# BCProjectBoardV2.net
KiCad netlist of a schematic drawn in EAGLE
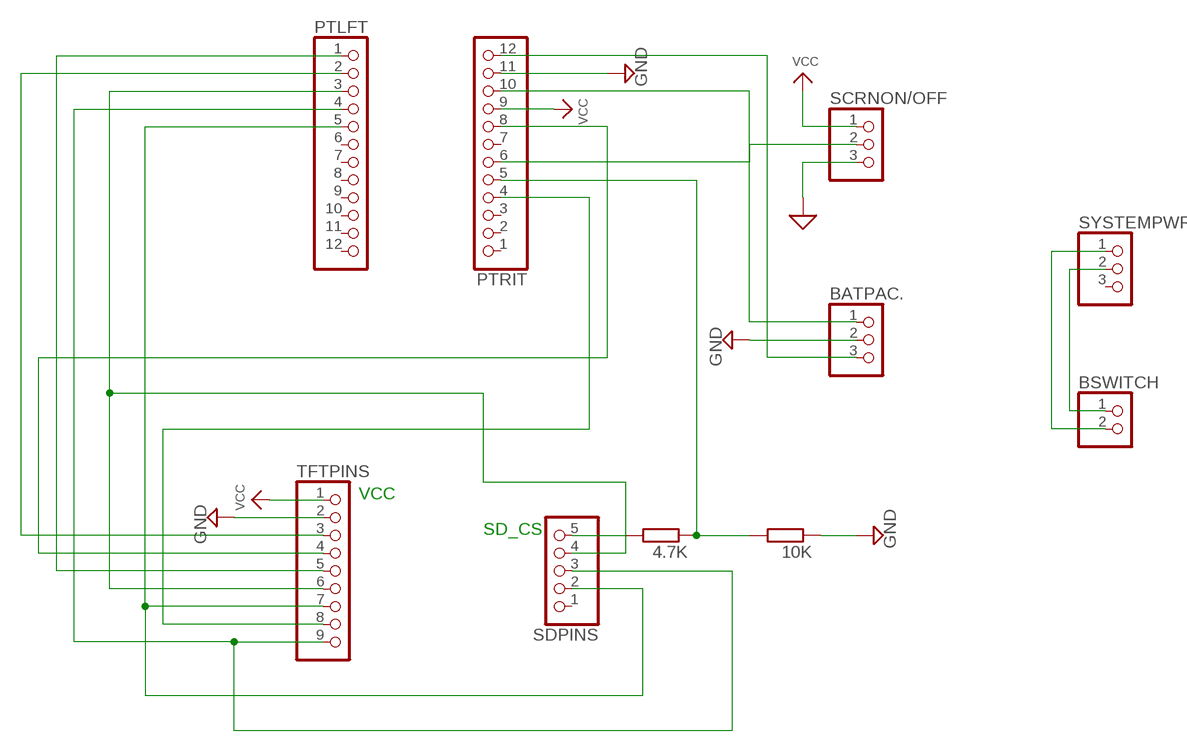
[diagram p0: schematic, sheet 1]

(export (version "E")
  (design (tool "Eeschema 10.0.6"))
  (components
    (comp (ref "4.7K")
      (value "R-EU_0204/5")
      (footprint "eagle-import:0204_5")
      (libsource (lib "eagle-import") (part "R-EU_0204/5"))
    )
    (comp (ref "10K")
      (value "R-EU_0204/5")
      (footprint "eagle-import:0204_5")
      (libsource (lib "eagle-import") (part "R-EU_0204/5"))
    )
    (comp (ref "BATPAC.")
      (value "PINHD-1X3")
      (footprint "eagle-import:1X03")
      (libsource (lib "eagle-import") (part "PINHD-1X3"))
    )
    (comp (ref "BSWITCH")
      (value "PINHD-1X2")
      (footprint "eagle-import:1X02")
      (libsource (lib "eagle-import") (part "PINHD-1X2"))
    )
    (comp (ref "PTLFT")
      (value "PINHD-1X12")
      (footprint "eagle-import:1X12")
      (libsource (lib "eagle-import") (part "PINHD-1X12"))
    )
    (comp (ref "PTRIT")
      (value "PINHD-1X12")
      (footprint "eagle-import:1X12")
      (libsource (lib "eagle-import") (part "PINHD-1X12"))
    )
    (comp (ref "SCRNON/OFF")
      (value "PINHD-1X3")
      (footprint "eagle-import:1X03")
      (libsource (lib "eagle-import") (part "PINHD-1X3"))
    )
    (comp (ref "SDPINS")
      (value "PINHD-1X5")
      (footprint "eagle-import:1X05")
      (libsource (lib "eagle-import") (part "PINHD-1X5"))
    )
    (comp (ref "SYSTEMPWR")
      (value "PINHD-1X3")
      (footprint "eagle-import:1X03")
      (libsource (lib "eagle-import") (part "PINHD-1X3"))
    )
    (comp (ref "TFTPINS")
      (value "PINHD-1X9")
      (footprint "eagle-import:1X09")
      (libsource (lib "eagle-import") (part "PINHD-1X9"))
    )
  )
  (nets
    (net (code "1") (name "GND") (class "Default")
      (node (ref "10K") (pin "1") (pinfunction "1_1") (pintype "passive"))
      (node (ref "BATPAC.") (pin "2") (pinfunction "2_2") (pintype "passive"))
      (node (ref "PTRIT") (pin "11") (pinfunction "11_11") (pintype "passive"))
      (node (ref "SCRNON/OFF") (pin "3") (pinfunction "3_3") (pintype "passive"))
      (node (ref "TFTPINS") (pin "2") (pinfunction "2_2") (pintype "passive"))
    )
    (net (code "2") (name "Net-(4.7K-Pad2)") (class "Default")
      (node (ref "4.7K") (pin "2") (pinfunction "2_2") (pintype "passive"))
      (node (ref "SDPINS") (pin "5") (pinfunction "5_5") (pintype "passive"))
    )
    (net (code "3") (name "Net-(10K-Pad2)") (class "Default")
      (node (ref "10K") (pin "2") (pinfunction "2_2") (pintype "passive"))
      (node (ref "4.7K") (pin "1") (pinfunction "1_1") (pintype "passive"))
      (node (ref "PTRIT") (pin "5") (pinfunction "5_5") (pintype "passive"))
    )
    (net (code "4") (name "Net-(BATPAC.-Pad1)") (class "Default")
      (node (ref "BATPAC.") (pin "1") (pinfunction "1_1") (pintype "passive"))
      (node (ref "PTRIT") (pin "10") (pinfunction "10_10") (pintype "passive"))
    )
    (net (code "5") (name "Net-(BATPAC.-Pad3)") (class "Default")
      (node (ref "BATPAC.") (pin "3") (pinfunction "3_3") (pintype "passive"))
      (node (ref "PTRIT") (pin "12") (pinfunction "12_12") (pintype "passive"))
    )
    (net (code "6") (name "Net-(BSWITCH-Pad1)") (class "Default")
      (node (ref "BSWITCH") (pin "1") (pinfunction "1_1") (pintype "passive"))
      (node (ref "SYSTEMPWR") (pin "2") (pinfunction "2_2") (pintype "passive"))
    )
    (net (code "7") (name "Net-(BSWITCH-Pad2)") (class "Default")
      (node (ref "BSWITCH") (pin "2") (pinfunction "2_2") (pintype "passive"))
      (node (ref "SYSTEMPWR") (pin "1") (pinfunction "1_1") (pintype "passive"))
    )
    (net (code "8") (name "Net-(PTLFT-Pad1)") (class "Default")
      (node (ref "PTLFT") (pin "1") (pinfunction "1_1") (pintype "passive"))
      (node (ref "TFTPINS") (pin "5") (pinfunction "5_5") (pintype "passive"))
    )
    (net (code "9") (name "Net-(PTLFT-Pad2)") (class "Default")
      (node (ref "PTLFT") (pin "2") (pinfunction "2_2") (pintype "passive"))
      (node (ref "TFTPINS") (pin "3") (pinfunction "3_3") (pintype "passive"))
    )
    (net (code "10") (name "Net-(PTLFT-Pad3)") (class "Default")
      (node (ref "PTLFT") (pin "3") (pinfunction "3_3") (pintype "passive"))
      (node (ref "SDPINS") (pin "4") (pinfunction "4_4") (pintype "passive"))
      (node (ref "TFTPINS") (pin "6") (pinfunction "6_6") (pintype "passive"))
    )
    (net (code "11") (name "Net-(PTLFT-Pad4)") (class "Default")
      (node (ref "PTLFT") (pin "4") (pinfunction "4_4") (pintype "passive"))
      (node (ref "SDPINS") (pin "3") (pinfunction "3_3") (pintype "passive"))
      (node (ref "TFTPINS") (pin "9") (pinfunction "9_9") (pintype "passive"))
    )
    (net (code "12") (name "Net-(PTLFT-Pad5)") (class "Default")
      (node (ref "PTLFT") (pin "5") (pinfunction "5_5") (pintype "passive"))
      (node (ref "SDPINS") (pin "2") (pinfunction "2_2") (pintype "passive"))
      (node (ref "TFTPINS") (pin "7") (pinfunction "7_7") (pintype "passive"))
    )
    (net (code "13") (name "Net-(PTRIT-Pad4)") (class "Default")
      (node (ref "PTRIT") (pin "4") (pinfunction "4_4") (pintype "passive"))
      (node (ref "TFTPINS") (pin "8") (pinfunction "8_8") (pintype "passive"))
    )
    (net (code "14") (name "Net-(PTRIT-Pad6)") (class "Default")
      (node (ref "PTRIT") (pin "6") (pinfunction "6_6") (pintype "passive"))
      (node (ref "SCRNON/OFF") (pin "2") (pinfunction "2_2") (pintype "passive"))
    )
    (net (code "15") (name "Net-(PTRIT-Pad8)") (class "Default")
      (node (ref "PTRIT") (pin "8") (pinfunction "8_8") (pintype "passive"))
      (node (ref "TFTPINS") (pin "4") (pinfunction "4_4") (pintype "passive"))
    )
    (net (code "16") (name "VCC") (class "Default")
      (node (ref "PTRIT") (pin "9") (pinfunction "9_9") (pintype "passive"))
      (node (ref "SCRNON/OFF") (pin "1") (pinfunction "1_1") (pintype "passive"))
      (node (ref "TFTPINS") (pin "1") (pinfunction "1_1") (pintype "passive"))
    )
    (net (code "17") (name "unconnected-(PTLFT-Pad6)") (class "Default")
      (node (ref "PTLFT") (pin "6") (pinfunction "6_6") (pintype "passive"))
    )
    (net (code "18") (name "unconnected-(PTLFT-Pad7)") (class "Default")
      (node (ref "PTLFT") (pin "7") (pinfunction "7_7") (pintype "passive"))
    )
    (net (code "19") (name "unconnected-(PTLFT-Pad8)") (class "Default")
      (node (ref "PTLFT") (pin "8") (pinfunction "8_8") (pintype "passive"))
    )
    (net (code "20") (name "unconnected-(PTLFT-Pad9)") (class "Default")
      (node (ref "PTLFT") (pin "9") (pinfunction "9_9") (pintype "passive"))
    )
    (net (code "21") (name "unconnected-(PTLFT-Pad10)") (class "Default")
      (node (ref "PTLFT") (pin "10") (pinfunction "10_10") (pintype "passive"))
    )
    (net (code "22") (name "unconnected-(PTLFT-Pad11)") (class "Default")
      (node (ref "PTLFT") (pin "11") (pinfunction "11_11") (pintype "passive"))
    )
    (net (code "23") (name "unconnected-(PTLFT-Pad12)") (class "Default")
      (node (ref "PTLFT") (pin "12") (pinfunction "12_12") (pintype "passive"))
    )
    (net (code "24") (name "unconnected-(PTRIT-Pad1)") (class "Default")
      (node (ref "PTRIT") (pin "1") (pinfunction "1_1") (pintype "passive"))
    )
    (net (code "25") (name "unconnected-(PTRIT-Pad2)") (class "Default")
      (node (ref "PTRIT") (pin "2") (pinfunction "2_2") (pintype "passive"))
    )
    (net (code "26") (name "unconnected-(PTRIT-Pad3)") (class "Default")
      (node (ref "PTRIT") (pin "3") (pinfunction "3_3") (pintype "passive"))
    )
    (net (code "27") (name "unconnected-(PTRIT-Pad7)") (class "Default")
      (node (ref "PTRIT") (pin "7") (pinfunction "7_7") (pintype "passive"))
    )
    (net (code "28") (name "unconnected-(SDPINS-Pad1)") (class "Default")
      (node (ref "SDPINS") (pin "1") (pinfunction "1_1") (pintype "passive"))
    )
    (net (code "29") (name "unconnected-(SYSTEMPWR-Pad3)") (class "Default")
      (node (ref "SYSTEMPWR") (pin "3") (pinfunction "3_3") (pintype "passive"))
    )
  )
)
